# 10_Misc.net
KiCad netlist of a schematic drawn in Altium Designer
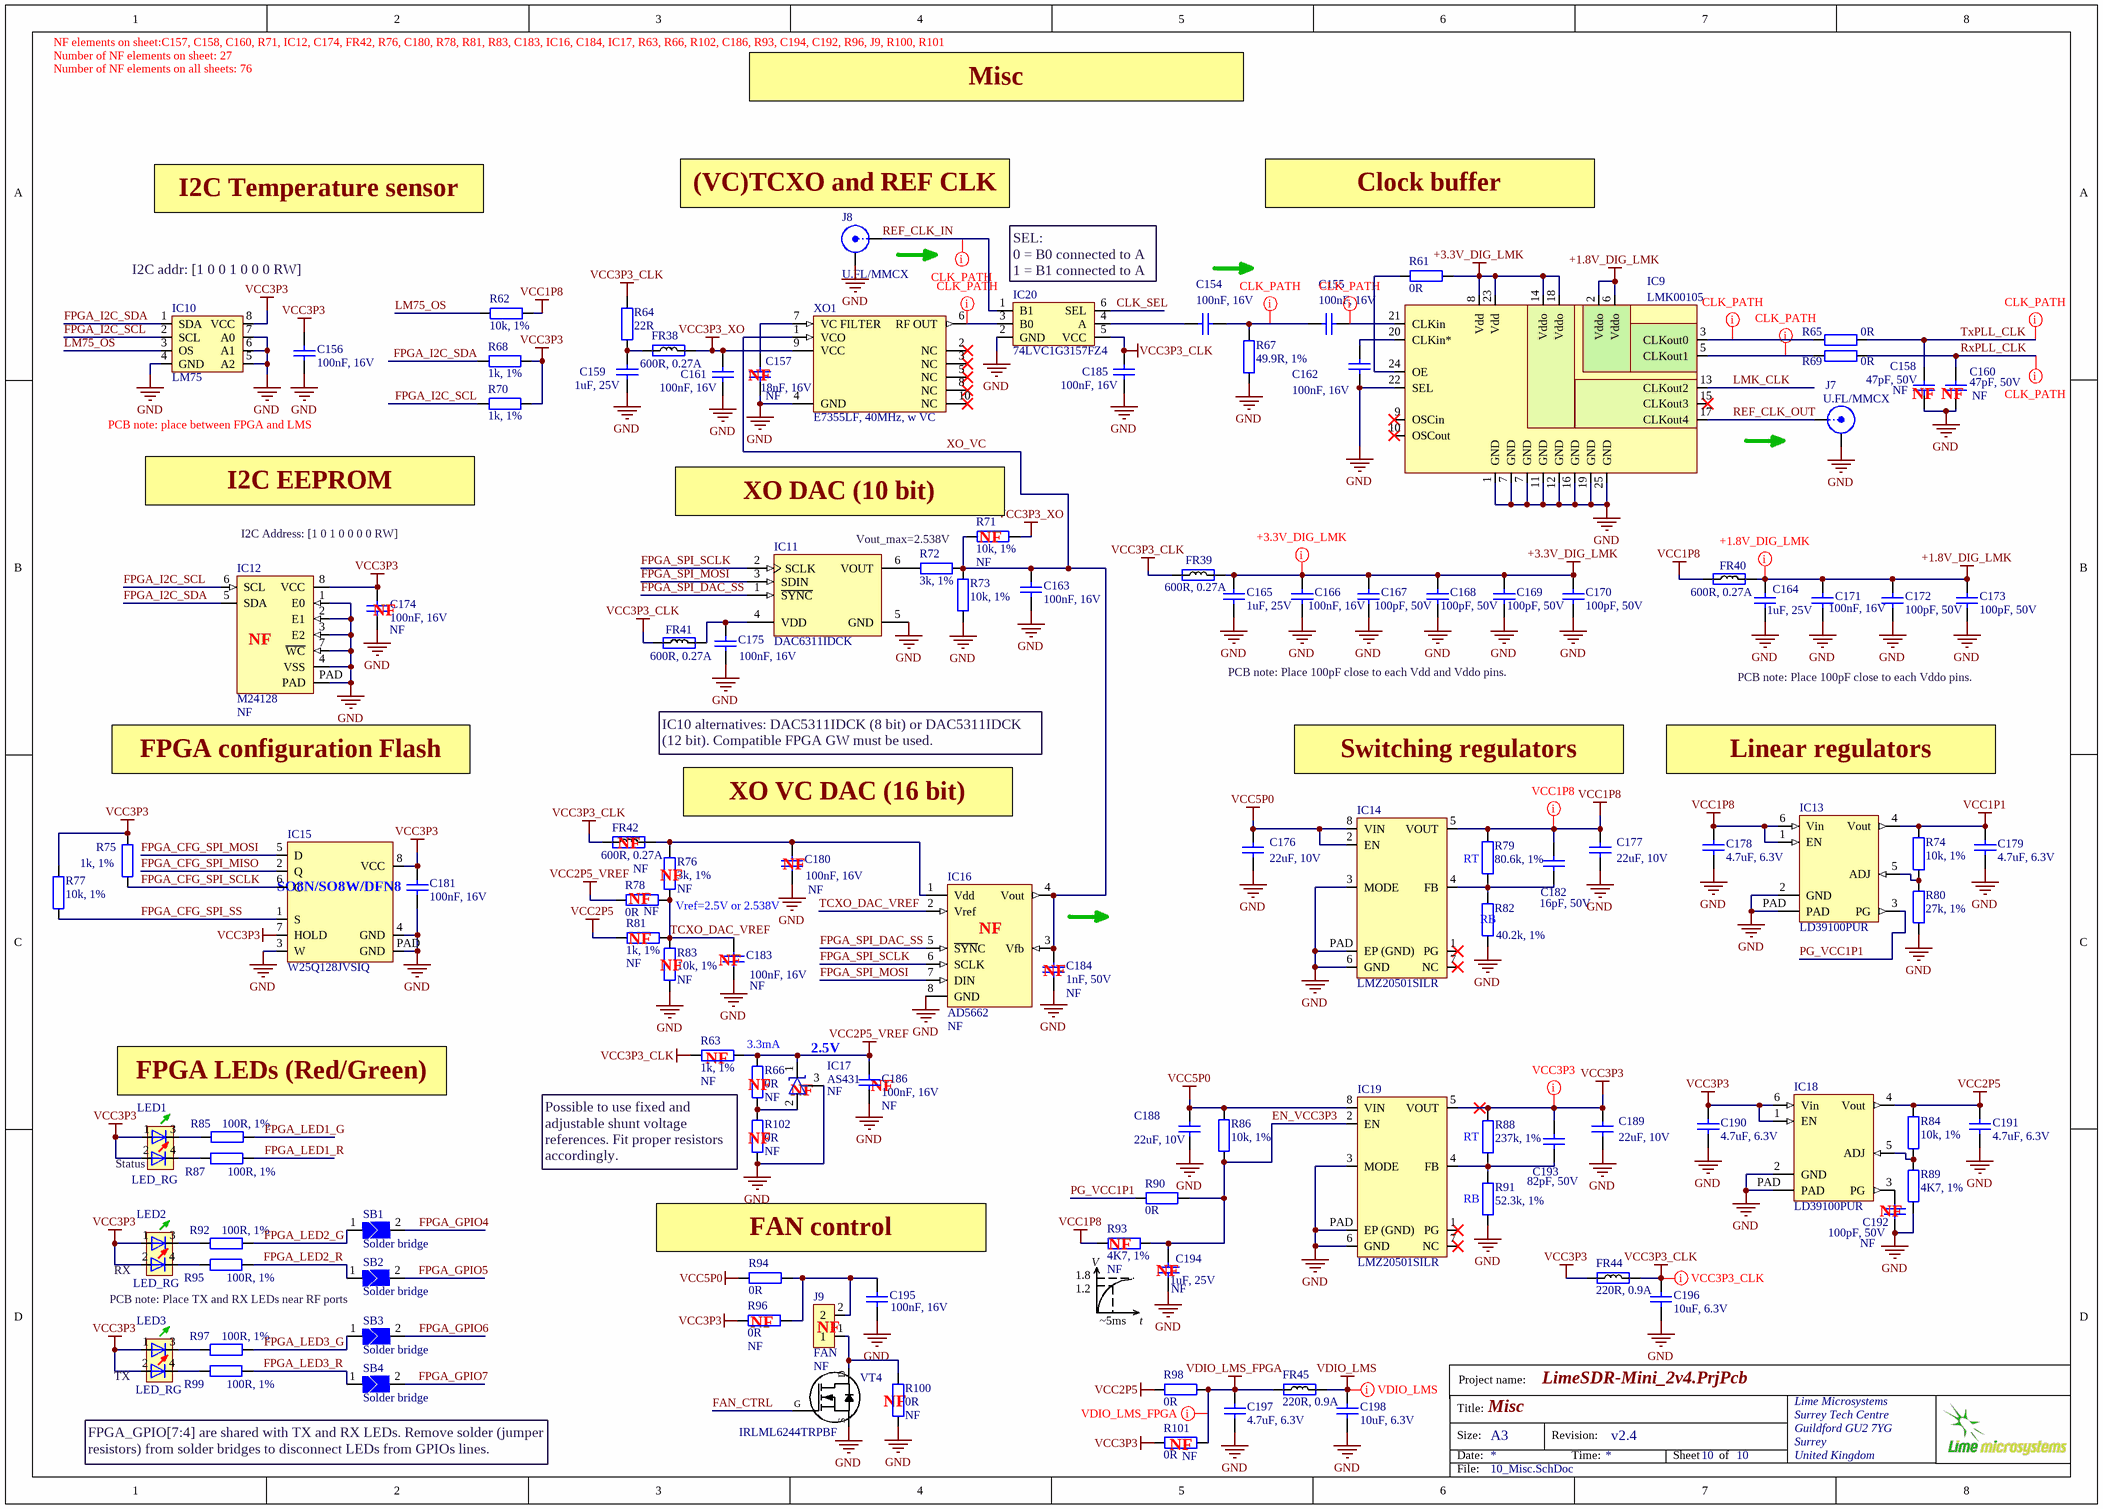
[diagram p0: 10_Misc.SchDoc]

(export (version "E")
  (design (tool "Eeschema 10.0.6"))
  (components
    (comp (ref "C154")
      (value "100nF, 16V")
      (footprint "CAP0402")
      (fields
        (field (name "MANUFACTURER") "Murata Electronics")
        (field (name "TOLERANCE") "10 %")
        (field (name "MANUFACTURER PART NUMBER") "GRM155R71C104KA88D")
      )
      (libsource (lib "LimeMicroAltiumLib_schLib") (part "Cap_0402"))
    )
    (comp (ref "C155")
      (value "100nF, 16V")
      (footprint "CAP0402")
      (fields
        (field (name "MANUFACTURER") "Murata Electronics")
        (field (name "TOLERANCE") "10 %")
        (field (name "MANUFACTURER PART NUMBER") "GRM155R71C104KA88D")
      )
      (libsource (lib "LimeMicroAltiumLib_schLib") (part "Cap_0402"))
    )
    (comp (ref "C156")
      (value "100nF, 16V")
      (footprint "CAP0402")
      (fields
        (field (name "TOLERANCE") "10 %")
        (field (name "MANUFACTURER") "Murata Electronics")
        (field (name "MANUFACTURER PART NUMBER") "GRM155R71C104KA88D")
      )
      (libsource (lib "LimeFPGAboard_schLib") (part "Cap_0603"))
    )
    (comp (ref "C157")
      (value "18nF, 16V")
      (footprint "CAP0402")
      (fields
        (field (name "ASSEMBLY INFO") "NF")
        (field (name "MANUFACTURER") "Yageo")
        (field (name "TOLERANCE") "±10%")
      )
      (libsource (lib "LimeMicroAltiumLib_schLib") (part "Cap_0402"))
    )
    (comp (ref "C158")
      (value "47pF, 50V")
      (footprint "CAP0402")
      (fields
        (field (name "TOLERANCE") "±1%")
        (field (name "MANUFACTURER") "TDK Corporation")
        (field (name "ASSEMBLY INFO") "NF")
      )
      (libsource (lib "LimeMicroAltiumLib_schLib") (part "Cap_0402"))
    )
    (comp (ref "C159")
      (value "1uF, 25V")
      (footprint "CAP0402")
      (fields (field (name "MANUFACTURER") "TDK"))
      (libsource (lib "LimeMicroAltiumLib_schLib") (part "Cap_0402"))
    )
    (comp (ref "C160")
      (value "47pF, 50V")
      (footprint "CAP0402")
      (fields
        (field (name "TOLERANCE") "±1%")
        (field (name "MANUFACTURER") "TDK Corporation")
        (field (name "ASSEMBLY INFO") "NF")
      )
      (libsource (lib "LimeMicroAltiumLib_schLib") (part "Cap_0402"))
    )
    (comp (ref "C161")
      (value "100nF, 16V")
      (footprint "CAP0402")
      (fields
        (field (name "MANUFACTURER") "Murata Electronics")
        (field (name "TOLERANCE") "10 %")
        (field (name "MANUFACTURER PART NUMBER") "GRM155R71C104KA88D")
      )
      (libsource (lib "LimeMicroAltiumLib_schLib") (part "Cap_0402"))
    )
    (comp (ref "C162")
      (value "100nF, 16V")
      (footprint "CAP0402")
      (fields
        (field (name "MANUFACTURER") "Murata Electronics")
        (field (name "TOLERANCE") "10 %")
        (field (name "MANUFACTURER PART NUMBER") "GRM155R71C104KA88D")
      )
      (libsource (lib "LimeMicroAltiumLib_schLib") (part "Cap_0402"))
    )
    (comp (ref "C163")
      (value "100nF, 16V")
      (footprint "CAP0402")
      (fields
        (field (name "MANUFACTURER") "Murata Electronics")
        (field (name "TOLERANCE") "10 %")
        (field (name "MANUFACTURER PART NUMBER") "GRM155R71C104KA88D")
      )
      (libsource (lib "LimeMicroAltiumLib_schLib") (part "Cap_0402"))
    )
    (comp (ref "C164")
      (value "1uF, 25V")
      (footprint "CAP0402")
      (fields (field (name "MANUFACTURER") "TDK"))
      (libsource (lib "LimeMicroAltiumLib_schLib") (part "Cap_0402"))
    )
    (comp (ref "C165")
      (value "1uF, 25V")
      (footprint "CAP0402")
      (fields (field (name "MANUFACTURER") "TDK"))
      (libsource (lib "LimeMicroAltiumLib_schLib") (part "Cap_0402"))
    )
    (comp (ref "C166")
      (value "100nF, 16V")
      (footprint "CAP0402")
      (fields
        (field (name "MANUFACTURER") "Murata Electronics")
        (field (name "TOLERANCE") "10 %")
        (field (name "MANUFACTURER PART NUMBER") "GRM155R71C104KA88D")
      )
      (libsource (lib "LimeMicroAltiumLib_schLib") (part "Cap_0402"))
    )
    (comp (ref "C167")
      (value "100pF, 50V")
      (footprint "CAP0402")
      (fields (field (name "MANUFACTURER") "Yageo") (field (name "TOLERANCE") "±5%"))
      (libsource (lib "LimeMicroAltiumLib_schLib") (part "Cap_0402"))
    )
    (comp (ref "C168")
      (value "100pF, 50V")
      (footprint "CAP0402")
      (fields (field (name "MANUFACTURER") "Yageo") (field (name "TOLERANCE") "±5%"))
      (libsource (lib "LimeMicroAltiumLib_schLib") (part "Cap_0402"))
    )
    (comp (ref "C169")
      (value "100pF, 50V")
      (footprint "CAP0402")
      (fields (field (name "MANUFACTURER") "Yageo") (field (name "TOLERANCE") "±5%"))
      (libsource (lib "LimeMicroAltiumLib_schLib") (part "Cap_0402"))
    )
    (comp (ref "C170")
      (value "100pF, 50V")
      (footprint "CAP0402")
      (fields (field (name "MANUFACTURER") "Yageo") (field (name "TOLERANCE") "±5%"))
      (libsource (lib "LimeMicroAltiumLib_schLib") (part "Cap_0402"))
    )
    (comp (ref "C171")
      (value "100nF, 16V")
      (footprint "CAP0402")
      (fields
        (field (name "MANUFACTURER") "Murata Electronics")
        (field (name "TOLERANCE") "10 %")
        (field (name "MANUFACTURER PART NUMBER") "GRM155R71C104KA88D")
      )
      (libsource (lib "LimeMicroAltiumLib_schLib") (part "Cap_0402"))
    )
    (comp (ref "C172")
      (value "100pF, 50V")
      (footprint "CAP0402")
      (fields (field (name "MANUFACTURER") "Yageo") (field (name "TOLERANCE") "±5%"))
      (libsource (lib "LimeMicroAltiumLib_schLib") (part "Cap_0402"))
    )
    (comp (ref "C173")
      (value "100pF, 50V")
      (footprint "CAP0402")
      (fields (field (name "MANUFACTURER") "Yageo") (field (name "TOLERANCE") "±5%"))
      (libsource (lib "LimeMicroAltiumLib_schLib") (part "Cap_0402"))
    )
    (comp (ref "C174")
      (value "100nF, 16V")
      (footprint "CAP0402")
      (fields
        (field (name "TOLERANCE") "10 %")
        (field (name "MANUFACTURER") "Murata Electronics")
        (field (name "MANUFACTURER PART NUMBER") "GRM155R71C104KA88D")
        (field (name "ASSEMBLY INFO") "NF")
      )
      (libsource (lib "LimeFPGAboard_schLib") (part "Cap_0603"))
    )
    (comp (ref "C175")
      (value "100nF, 16V")
      (footprint "CAP0402")
      (fields
        (field (name "TOLERANCE") "10 %")
        (field (name "MANUFACTURER") "Murata Electronics")
        (field (name "MANUFACTURER PART NUMBER") "GRM155R71C104KA88D")
      )
      (libsource (lib "LimeFPGAboard_schLib") (part "Cap_0603"))
    )
    (comp (ref "C176")
      (value "22uF, 10V")
      (footprint "CAP0603")
      (fields (field (name "TOLERANCE") "20 %") (field (name "MANUFACTURER") "TDK Corporation"))
      (libsource (lib "LimeFPGAboard_schLib") (part "Cap_0603"))
    )
    (comp (ref "C177")
      (value "22uF, 10V")
      (footprint "CAP0603")
      (fields (field (name "TOLERANCE") "20 %") (field (name "MANUFACTURER") "TDK Corporation"))
      (libsource (lib "LimeFPGAboard_schLib") (part "Cap_0603"))
    )
    (comp (ref "C178")
      (value "4.7uF, 6.3V")
      (footprint "CAP0402")
      (fields
        (field (name "MANUFACTURER") "Murata Electronics North America")
        (field (name "TOLERANCE") "±20%")
      )
      (libsource (lib "LimeMicroAltiumLib_schLib") (part "Cap_0402"))
    )
    (comp (ref "C179")
      (value "4.7uF, 6.3V")
      (footprint "CAP0402")
      (fields
        (field (name "MANUFACTURER") "Murata Electronics North America")
        (field (name "TOLERANCE") "±20%")
      )
      (libsource (lib "LimeMicroAltiumLib_schLib") (part "Cap_0402"))
    )
    (comp (ref "C180")
      (value "100nF, 16V")
      (footprint "CAP0402")
      (fields
        (field (name "TOLERANCE") "10 %")
        (field (name "MANUFACTURER") "Murata Electronics")
        (field (name "MANUFACTURER PART NUMBER") "GRM155R71C104KA88D")
        (field (name "ASSEMBLY INFO") "NF")
      )
      (libsource (lib "LimeFPGAboard_schLib") (part "Cap_0603"))
    )
    (comp (ref "C181")
      (value "100nF, 16V")
      (footprint "CAP0402")
      (fields
        (field (name "TOLERANCE") "10 %")
        (field (name "MANUFACTURER") "Murata Electronics")
        (field (name "MANUFACTURER PART NUMBER") "GRM155R71C104KA88D")
      )
      (libsource (lib "LimeFPGAboard_schLib") (part "Cap_0603"))
    )
    (comp (ref "C182")
      (value "16pF, 50V")
      (footprint "CAP0402")
      (fields (field (name "MANUFACTURER") "Yageo") (field (name "TOLERANCE") "5%"))
      (libsource (lib "LimeMicroAltiumLib_schLib") (part "Cap_0402"))
    )
    (comp (ref "C183")
      (value "100nF, 16V")
      (footprint "CAP0402")
      (fields
        (field (name "TOLERANCE") "10 %")
        (field (name "MANUFACTURER") "Murata Electronics")
        (field (name "ASSEMBLY INFO") "NF")
      )
      (libsource (lib "") (part "Cap_0603_1"))
    )
    (comp (ref "C184")
      (value "1nF, 50V")
      (footprint "CAP0402")
      (fields
        (field (name "ASSEMBLY INFO") "NF")
        (field (name "TOLERANCE") "10 %")
        (field (name "MANUFACTURER") "Murata Electronics")
      )
      (libsource (lib "") (part "Cap_0402_1"))
    )
    (comp (ref "C185")
      (value "100nF, 16V")
      (footprint "CAP0402")
      (fields
        (field (name "MANUFACTURER") "Murata Electronics")
        (field (name "TOLERANCE") "10 %")
        (field (name "MANUFACTURER PART NUMBER") "GRM155R71C104KA88D")
      )
      (libsource (lib "LimeMicroAltiumLib_schLib") (part "Cap_0402"))
    )
    (comp (ref "C186")
      (value "100nF, 16V")
      (footprint "CAP0402")
      (fields
        (field (name "TOLERANCE") "10 %")
        (field (name "MANUFACTURER") "Murata Electronics")
        (field (name "ASSEMBLY INFO") "NF")
      )
      (libsource (lib "") (part "Cap_0603_1"))
    )
    (comp (ref "C188")
      (value "22uF, 10V")
      (footprint "CAP0603")
      (fields (field (name "TOLERANCE") "20 %") (field (name "MANUFACTURER") "TDK Corporation"))
      (libsource (lib "LimeFPGAboard_schLib") (part "Cap_0603"))
    )
    (comp (ref "C189")
      (value "22uF, 10V")
      (footprint "CAP0603")
      (fields (field (name "TOLERANCE") "20 %") (field (name "MANUFACTURER") "TDK Corporation"))
      (libsource (lib "LimeFPGAboard_schLib") (part "Cap_0603"))
    )
    (comp (ref "C190")
      (value "4.7uF, 6.3V")
      (footprint "CAP0402")
      (fields
        (field (name "MANUFACTURER") "Murata Electronics North America")
        (field (name "TOLERANCE") "±20%")
      )
      (libsource (lib "LimeMicroAltiumLib_schLib") (part "Cap_0402"))
    )
    (comp (ref "C191")
      (value "4.7uF, 6.3V")
      (footprint "CAP0402")
      (fields
        (field (name "MANUFACTURER") "Murata Electronics North America")
        (field (name "TOLERANCE") "±20%")
      )
      (libsource (lib "LimeMicroAltiumLib_schLib") (part "Cap_0402"))
    )
    (comp (ref "C192")
      (value "100pF, 50V")
      (footprint "CAP0402")
      (fields
        (field (name "ASSEMBLY INFO") "NF")
        (field (name "MANUFACTURER") "Yageo")
        (field (name "TOLERANCE") "±5%")
      )
      (libsource (lib "LimeMicroAltiumLib_schLib") (part "Cap_0402"))
    )
    (comp (ref "C193")
      (value "82pF, 50V")
      (footprint "CAP0402")
      (fields (field (name "MANUFACTURER") "Taiyo Yuden"))
      (libsource (lib "LimeMicroAltiumLib_schLib") (part "Cap_0402"))
    )
    (comp (ref "C194")
      (value "1uF, 25V")
      (footprint "CAP0402")
      (fields (field (name "ASSEMBLY INFO") "NF") (field (name "MANUFACTURER") "TDK"))
      (libsource (lib "LimeMicroAltiumLib_schLib") (part "Cap_0402"))
    )
    (comp (ref "C195")
      (value "100nF, 16V")
      (footprint "CAP0402")
      (fields
        (field (name "TOLERANCE") "10 %")
        (field (name "MANUFACTURER") "Murata Electronics")
        (field (name "MANUFACTURER PART NUMBER") "GRM155R71C104KA88D")
      )
      (libsource (lib "LimeFPGAboard_schLib") (part "Cap_0603"))
    )
    (comp (ref "C196")
      (value "10uF, 6.3V")
      (footprint "CAP0603")
      (fields (field (name "TOLERANCE") "±20%") (field (name "MANUFACTURER") "Yageo"))
      (libsource (lib "LimeFPGAboard_schLib") (part "Cap_0603"))
    )
    (comp (ref "C197")
      (value "4.7uF, 6.3V")
      (footprint "CAP0402")
      (fields
        (field (name "MANUFACTURER") "Murata Electronics North America")
        (field (name "TOLERANCE") "±20%")
      )
      (libsource (lib "LimeMicroAltiumLib_schLib") (part "Cap_0402"))
    )
    (comp (ref "C198")
      (value "10uF, 6.3V")
      (footprint "CAP0603")
      (fields (field (name "TOLERANCE") "±20%") (field (name "MANUFACTURER") "Yageo"))
      (libsource (lib "LimeFPGAboard_schLib") (part "Cap_0603"))
    )
    (comp (ref "FR38")
      (value "600R, 0.27A")
      (footprint "RES0201")
      (fields (field (name "MANUFACTURER") "Taiyo Yuden"))
      (libsource (lib "LimeMicroAltiumLib_schLib") (part "Ferrite"))
    )
    (comp (ref "FR39")
      (value "600R, 0.27A")
      (footprint "RES0201")
      (fields (field (name "MANUFACTURER") "Taiyo Yuden"))
      (libsource (lib "LimeMicroAltiumLib_schLib") (part "Ferrite"))
    )
    (comp (ref "FR40")
      (value "600R, 0.27A")
      (footprint "RES0201")
      (fields (field (name "MANUFACTURER") "Taiyo Yuden"))
      (libsource (lib "LimeMicroAltiumLib_schLib") (part "Ferrite"))
    )
    (comp (ref "FR41")
      (value "600R, 0.27A")
      (footprint "RES0201")
      (fields (field (name "MANUFACTURER") "Taiyo Yuden"))
      (libsource (lib "LimeMicroAltiumLib_schLib") (part "Ferrite"))
    )
    (comp (ref "FR42")
      (value "600R, 0.27A")
      (footprint "RES0201")
      (fields (field (name "MANUFACTURER") "Taiyo Yuden") (field (name "ASSEMBLY INFO") "NF"))
      (libsource (lib "LimeMicroAltiumLib_schLib") (part "Ferrite"))
    )
    (comp (ref "FR44")
      (value "220R, 0.9A")
      (footprint "RES0402")
      (fields (field (name "MANUFACTURER") "TDK Corporation"))
      (libsource (lib "LimeFPGAboard_schLib") (part "Ferrite"))
    )
    (comp (ref "FR45")
      (value "220R, 0.9A")
      (footprint "RES0402")
      (fields (field (name "MANUFACTURER") "TDK Corporation"))
      (libsource (lib "LimeFPGAboard_schLib") (part "Ferrite"))
    )
    (comp (ref "IC9")
      (value "LMK00105")
      (footprint "LMK00105SQ")
      (fields (field (name "MANUFACTURER") "Texas Instruments"))
      (libsource (lib "LimeMicroAltiumLib_schLib") (part "LMK00105"))
    )
    (comp (ref "IC10")
      (value "LM75")
      (footprint "HWSON8_LM75")
      (fields (field (name "MANUFACTURER") "NXP Semiconductors"))
      (libsource (lib "LimeMicroAltiumLib_schLib") (part "LM75"))
    )
    (comp (ref "IC11")
      (value "DAC6311IDCK")
      (footprint "AD5601_SOT23-6")
      (fields (field (name "MANUFACTURER") "Texas Instruments"))
      (libsource (lib "LimeMicroAltiumLib_schLib") (part "AD5601BKSZ-REEL7"))
    )
    (comp (ref "IC12")
      (value "M24128")
      (footprint "M24128-DFMC6TG")
      (fields (field (name "MANUFACTURER") "STMicroelectronics") (field (name "ASSEMBLY INFO") "NF"))
      (libsource (lib "LimeMicroAltiumLib_schLib") (part "M24128-DFMC6TG"))
    )
    (comp (ref "IC13")
      (value "LD39100PUR")
      (footprint "LD39100PUR")
      (fields (field (name "MANUFACTURER") "STMicroelectronics"))
      (libsource (lib "LimeMicroAltiumLib_schLib") (part "LD39100PUR"))
    )
    (comp (ref "IC14")
      (value "LMZ20501SILR")
      (footprint "LMZ20501SILR_DC-DC_8-SMD")
      (fields (field (name "MANUFACTURER") "Texas Instruments"))
      (libsource (lib "LimeMicroAltiumLib_schLib_r04") (part "LMZ20501SILR_DC-DC"))
    )
    (comp (ref "IC15")
      (value "W25Q128JVSIQ")
      (footprint "S25FL164K_WSON8_DFN6")
      (fields (field (name "MANUFACTURER") "Winbond"))
      (libsource (lib "LimeMicroAltiumLib_schLib_r03") (part "M25P40_with_pad"))
    )
    (comp (ref "IC16")
      (value "AD5662")
      (footprint "AD5662_SOT23-8")
      (fields (field (name "MANUFACTURER") "Analog Devices Inc.") (field (name "ASSEMBLY INFO") "NF"))
      (libsource (lib "LimeMicroAltiumLib_schLib") (part "AD5662"))
    )
    (comp (ref "IC17")
      (value "AS431")
      (footprint "SOT23-3_V3")
      (fields
        (field (name "ASSEMBLY INFO") "NF")
        (field (name "MANUFACTURER") "Diodes")
        (field (name "TOLERANCE") "0.5%")
      )
      (libsource (lib "LimeMicroAltiumLib_schLib_r05") (part "VOLTAGE_REFERENCE_UNIVERSAL"))
    )
    (comp (ref "IC18")
      (value "LD39100PUR")
      (footprint "LD39100PUR")
      (fields (field (name "MANUFACTURER") "STMicroelectronics"))
      (libsource (lib "LimeMicroAltiumLib_schLib") (part "LD39100PUR"))
    )
    (comp (ref "IC19")
      (value "LMZ20501SILR")
      (footprint "LMZ20501SILR_DC-DC_8-SMD")
      (fields (field (name "MANUFACTURER") "Texas Instruments"))
      (libsource (lib "LimeMicroAltiumLib_schLib_r04") (part "LMZ20501SILR_DC-DC"))
    )
    (comp (ref "IC20")
      (value "74LVC1G3157FZ4")
      (footprint "74LVC1G3157FZ4_SPDT_SW_DFN1410-6")
      (fields (field (name "MANUFACTURER") "Diodes"))
      (libsource (lib "LimeMicroAltiumLib_schLib_r04") (part "74LVC1G3157FZ4_SPDT_SW"))
    )
    (comp (ref "J7")
      (value "U.FL/MMCX")
      (footprint "MMCX_UFL_conn_u")
      (description "CONN UMC RCPT STR 50 OHM SMD")
      (fields (field (name "MANUFACTURER") "Molex, LLC"))
      (libsource (lib "LimeMicroAltiumLib_schLib") (part "RF_IF_connector"))
    )
    (comp (ref "J8")
      (value "U.FL/MMCX")
      (footprint "MMCX_UFL_conn_u")
      (description "CONN UMC RCPT STR 50 OHM SMD")
      (fields (field (name "MANUFACTURER") "Molex, LLC"))
      (libsource (lib "LimeMicroAltiumLib_schLib") (part "RF_IF_connector"))
    )
    (comp (ref "J9")
      (value "FAN")
      (footprint "Header2x1_TH_v2")
      (fields (field (name "ASSEMBLY INFO") "NF") (field (name "MANUFACTURER") "3M"))
      (libsource (lib "LimeFPGAboard_schLib") (part "Jumper"))
    )
    (comp (ref "LED1")
      (value "LED_RG")
      (footprint "LED-2x0603")
      (fields (field (name "MANUFACTURER") "Avago Technologies US Inc."))
      (libsource (lib "LimeMicroAltiumLib_schLib") (part "LED_green_red_SMD"))
    )
    (comp (ref "LED2")
      (value "LED_RG")
      (footprint "LED-2x0603")
      (fields (field (name "MANUFACTURER") "Avago Technologies US Inc."))
      (libsource (lib "LimeMicroAltiumLib_schLib") (part "LED_green_red_SMD"))
    )
    (comp (ref "LED3")
      (value "LED_RG")
      (footprint "LED-2x0603")
      (fields (field (name "MANUFACTURER") "Avago Technologies US Inc."))
      (libsource (lib "LimeMicroAltiumLib_schLib") (part "LED_green_red_SMD"))
    )
    (comp (ref "R61")
      (value "0R")
      (footprint "RES0402")
      (fields (field (name "MANUFACTURER") "Yageo") (field (name "TOLERANCE") "Jumper"))
      (libsource (lib "") (part "Res_0402_1"))
    )
    (comp (ref "R62")
      (value "10k, 1%")
      (footprint "RES0402")
      (fields (field (name "MANUFACTURER") "Yageo") (field (name "TOLERANCE") "±1%"))
      (libsource (lib "") (part "Res_0402_1"))
    )
    (comp (ref "R63")
      (value "1k, 1%")
      (footprint "RES0402")
      (fields
        (field (name "ASSEMBLY INFO") "NF")
        (field (name "MANUFACTURER") "Stackpole Electronics Inc")
        (field (name "TOLERANCE") "±1%")
      )
      (libsource (lib "") (part "Res_0402_1"))
    )
    (comp (ref "R64")
      (value "22R")
      (footprint "RES0402")
      (fields (field (name "TOLERANCE") "±1%") (field (name "MANUFACTURER") "Yageo"))
      (libsource (lib "LimeFPGAboard_schLib") (part "Res_0402"))
    )
    (comp (ref "R65")
      (value "0R")
      (footprint "RES0402")
      (fields (field (name "MANUFACTURER") "Yageo") (field (name "TOLERANCE") "Jumper"))
      (libsource (lib "LimeFPGAboard_schLib") (part "Res_0402"))
    )
    (comp (ref "R66")
      (value "0R")
      (footprint "RES0402")
      (fields
        (field (name "ASSEMBLY INFO") "NF")
        (field (name "MANUFACTURER") "Yageo")
        (field (name "TOLERANCE") "Jumper")
      )
      (libsource (lib "") (part "Res_0402_1"))
    )
    (comp (ref "R67")
      (value "49.9R, 1%")
      (footprint "RES0402")
      (fields
        (field (name "TOLERANCE") "±1%")
        (field (name "MANUFACTURER") "Samsung Electro-Mechanics America, Inc.")
      )
      (libsource (lib "") (part "Res_0402_1"))
    )
    (comp (ref "R68")
      (value "1k, 1%")
      (footprint "RES0402")
      (fields (field (name "MANUFACTURER") "Stackpole Electronics Inc") (field (name "TOLERANCE") "±1%"))
      (libsource (lib "") (part "Res_0402_1"))
    )
    (comp (ref "R69")
      (value "0R")
      (footprint "RES0402")
      (fields (field (name "MANUFACTURER") "Yageo") (field (name "TOLERANCE") "Jumper"))
      (libsource (lib "LimeFPGAboard_schLib") (part "Res_0402"))
    )
    (comp (ref "R70")
      (value "1k, 1%")
      (footprint "RES0402")
      (fields (field (name "MANUFACTURER") "Stackpole Electronics Inc") (field (name "TOLERANCE") "±1%"))
      (libsource (lib "") (part "Res_0402_1"))
    )
    (comp (ref "R71")
      (value "10k, 1%")
      (footprint "RES0402")
      (fields
        (field (name "ASSEMBLY INFO") "NF")
        (field (name "MANUFACTURER") "Yageo")
        (field (name "TOLERANCE") "±1%")
      )
      (libsource (lib "") (part "Res_0402_1"))
    )
    (comp (ref "R72")
      (value "3k, 1%")
      (footprint "RES0402")
      (fields (field (name "TOLERANCE") "±1%") (field (name "MANUFACTURER") "Vishay Dale"))
      (libsource (lib "") (part "Res_0402_1"))
    )
    (comp (ref "R73")
      (value "10k, 1%")
      (footprint "RES0402")
      (fields (field (name "MANUFACTURER") "Yageo") (field (name "TOLERANCE") "±1%"))
      (libsource (lib "") (part "Res_0402_1"))
    )
    (comp (ref "R74")
      (value "10k, 1%")
      (footprint "RES0402")
      (fields (field (name "MANUFACTURER") "Yageo") (field (name "TOLERANCE") "±1%"))
      (libsource (lib "") (part "Res_0402_1"))
    )
    (comp (ref "R75")
      (value "1k, 1%")
      (footprint "RES0402")
      (fields (field (name "MANUFACTURER") "Stackpole Electronics Inc") (field (name "TOLERANCE") "±1%"))
      (libsource (lib "") (part "Res_0402_1"))
    )
    (comp (ref "R76")
      (value "3k, 1%")
      (footprint "RES0402")
      (fields
        (field (name "ASSEMBLY INFO") "NF")
        (field (name "TOLERANCE") "±1%")
        (field (name "MANUFACTURER") "Vishay Dale")
      )
      (libsource (lib "LimeMicroAltiumLib_schLib") (part "Res_0402"))
    )
    (comp (ref "R77")
      (value "10k, 1%")
      (footprint "RES0402")
      (fields (field (name "MANUFACTURER") "Yageo") (field (name "TOLERANCE") "±1%"))
      (libsource (lib "") (part "Res_0402_1"))
    )
    (comp (ref "R78")
      (value "0R")
      (footprint "RES0402")
      (fields
        (field (name "ASSEMBLY INFO") "NF")
        (field (name "MANUFACTURER") "Yageo")
        (field (name "TOLERANCE") "Jumper")
      )
      (libsource (lib "") (part "Res_0402_1"))
    )
    (comp (ref "R79")
      (value "80.6k, 1%")
      (footprint "RES0402")
      (fields (field (name "MANUFACTURER") "Stackpole Electronics") (field (name "TOLERANCE") "1%"))
      (libsource (lib "") (part "Res_0402_1"))
    )
    (comp (ref "R80")
      (value "27k, 1%")
      (footprint "RES0402")
      (fields (field (name "MANUFACTURER") "Yageo") (field (name "TOLERANCE") "1%"))
      (libsource (lib "LimeFPGAboard_schLib") (part "Res_0402"))
    )
    (comp (ref "R81")
      (value "1k, 1%")
      (footprint "RES0402")
      (fields
        (field (name "ASSEMBLY INFO") "NF")
        (field (name "MANUFACTURER") "Stackpole Electronics Inc")
        (field (name "TOLERANCE") "±1%")
      )
      (libsource (lib "LimeMicroAltiumLib_schLib") (part "Res_0402"))
    )
    (comp (ref "R82")
      (value "40.2k, 1%")
      (footprint "RES0402")
      (fields (field (name "MANUFACTURER") "Yageo") (field (name "TOLERANCE") "1%"))
      (libsource (lib "") (part "Res_0402_1"))
    )
    (comp (ref "R83")
      (value "10k, 1%")
      (footprint "RES0402")
      (fields
        (field (name "ASSEMBLY INFO") "NF")
        (field (name "MANUFACTURER") "Yageo")
        (field (name "TOLERANCE") "±1%")
      )
      (libsource (lib "LimeMicroAltiumLib_schLib") (part "Res_0402"))
    )
    (comp (ref "R84")
      (value "10k, 1%")
      (footprint "RES0402")
      (fields (field (name "MANUFACTURER") "Yageo") (field (name "TOLERANCE") "±1%"))
      (libsource (lib "") (part "Res_0402_1"))
    )
    (comp (ref "R85")
      (value "100R, 1%")
      (footprint "RES0402")
      (fields (field (name "TOLERANCE") "±1%") (field (name "MANUFACTURER") "Stackpole Electronics Inc."))
      (libsource (lib "") (part "Res_0402_1"))
    )
    (comp (ref "R86")
      (value "10k, 1%")
      (footprint "RES0402")
      (fields (field (name "MANUFACTURER") "Yageo") (field (name "TOLERANCE") "±1%"))
      (libsource (lib "") (part "Res_0402_1"))
    )
    (comp (ref "R87")
      (value "100R, 1%")
      (footprint "RES0402")
      (fields (field (name "TOLERANCE") "±1%") (field (name "MANUFACTURER") "Stackpole Electronics Inc."))
      (libsource (lib "") (part "Res_0402_1"))
    )
    (comp (ref "R88")
      (value "237k, 1%")
      (footprint "RES0402")
      (fields (field (name "MANUFACTURER") "Yageo") (field (name "TOLERANCE") "1%"))
      (libsource (lib "") (part "Res_0402_1"))
    )
    (comp (ref "R89")
      (value "4K7, 1%")
      (footprint "RES0402")
      (fields (field (name "MANUFACTURER") "Yageo") (field (name "TOLERANCE") "±1%"))
      (libsource (lib "LimeFPGAboard_schLib") (part "Res_0402"))
    )
    (comp (ref "R90")
      (value "0R")
      (footprint "RES0402")
      (fields (field (name "MANUFACTURER") "Yageo") (field (name "TOLERANCE") "Jumper"))
      (libsource (lib "") (part "Res_0402_1"))
    )
    (comp (ref "R91")
      (value "52.3k, 1%")
      (footprint "RES0402")
      (fields (field (name "MANUFACTURER") "Panasonic") (field (name "TOLERANCE") "1%"))
      (libsource (lib "") (part "Res_0402_1"))
    )
    (comp (ref "R92")
      (value "100R, 1%")
      (footprint "RES0402")
      (fields (field (name "TOLERANCE") "±1%") (field (name "MANUFACTURER") "Stackpole Electronics Inc."))
      (libsource (lib "") (part "Res_0402_1"))
    )
    (comp (ref "R93")
      (value "4K7, 1%")
      (footprint "RES0402")
      (fields
        (field (name "MANUFACTURER") "Yageo")
        (field (name "TOLERANCE") "±1%")
        (field (name "ASSEMBLY INFO") "NF")
      )
      (libsource (lib "LimeFPGAboard_schLib") (part "Res_0402"))
    )
    (comp (ref "R94")
      (value "0R")
      (footprint "RES0402")
      (fields (field (name "MANUFACTURER") "Yageo") (field (name "TOLERANCE") "Jumper"))
      (libsource (lib "") (part "Res_0402_1"))
    )
    (comp (ref "R95")
      (value "100R, 1%")
      (footprint "RES0402")
      (fields (field (name "TOLERANCE") "±1%") (field (name "MANUFACTURER") "Stackpole Electronics Inc."))
      (libsource (lib "") (part "Res_0402_1"))
    )
    (comp (ref "R96")
      (value "0R")
      (footprint "RES0402")
      (fields
        (field (name "ASSEMBLY INFO") "NF")
        (field (name "MANUFACTURER") "Yageo")
        (field (name "TOLERANCE") "Jumper")
      )
      (libsource (lib "") (part "Res_0402_1"))
    )
    (comp (ref "R97")
      (value "100R, 1%")
      (footprint "RES0402")
      (fields (field (name "TOLERANCE") "±1%") (field (name "MANUFACTURER") "Stackpole Electronics Inc."))
      (libsource (lib "") (part "Res_0402_1"))
    )
    (comp (ref "R98")
      (value "0R")
      (footprint "RES0402")
      (fields (field (name "MANUFACTURER") "Yageo") (field (name "TOLERANCE") "Jumper"))
      (libsource (lib "LimeFPGAboard_schLib") (part "Res_0402"))
    )
    (comp (ref "R99")
      (value "100R, 1%")
      (footprint "RES0402")
      (fields (field (name "TOLERANCE") "±1%") (field (name "MANUFACTURER") "Stackpole Electronics Inc."))
      (libsource (lib "") (part "Res_0402_1"))
    )
    (comp (ref "R100")
      (value "0R")
      (footprint "RES0402")
      (fields
        (field (name "ASSEMBLY INFO") "NF")
        (field (name "MANUFACTURER") "Yageo")
        (field (name "TOLERANCE") "Jumper")
      )
      (libsource (lib "") (part "Res_0402_1"))
    )
    (comp (ref "R101")
      (value "0R")
      (footprint "RES0402")
      (fields
        (field (name "MANUFACTURER") "Yageo")
        (field (name "ASSEMBLY INFO") "NF")
        (field (name "TOLERANCE") "Jumper")
      )
      (libsource (lib "LimeFPGAboard_schLib") (part "Res_0402"))
    )
    (comp (ref "R102")
      (value "0R")
      (footprint "RES0402")
      (fields
        (field (name "ASSEMBLY INFO") "NF")
        (field (name "MANUFACTURER") "Yageo")
        (field (name "TOLERANCE") "Jumper")
      )
      (libsource (lib "") (part "Res_0402_1"))
    )
    (comp (ref "SB1")
      (value "Solder bridge")
      (footprint "SOLDER_BRIDGE_TRIANGULAR_v2")
      (description "Can be shorted out using solder paste or 0402-1206 resistor")
      (fields (field (name "MANUFACTURER") "Yageo") (field (name "TOLERANCE") "Jumper"))
      (libsource (lib "LimeMicroAltiumLib_schLib_r03") (part "SOLDER_BRIDGE_TRIANGULAR"))
    )
    (comp (ref "SB2")
      (value "Solder bridge")
      (footprint "SOLDER_BRIDGE_TRIANGULAR_v2")
      (description "Can be shorted out using solder paste or 0402-1206 resistor")
      (fields (field (name "MANUFACTURER") "Yageo") (field (name "TOLERANCE") "Jumper"))
      (libsource (lib "LimeMicroAltiumLib_schLib_r03") (part "SOLDER_BRIDGE_TRIANGULAR"))
    )
    (comp (ref "SB3")
      (value "Solder bridge")
      (footprint "SOLDER_BRIDGE_TRIANGULAR_v2")
      (description "Can be shorted out using solder paste or 0402-1206 resistor")
      (fields (field (name "MANUFACTURER") "Yageo") (field (name "TOLERANCE") "Jumper"))
      (libsource (lib "LimeMicroAltiumLib_schLib_r03") (part "SOLDER_BRIDGE_TRIANGULAR"))
    )
    (comp (ref "SB4")
      (value "Solder bridge")
      (footprint "SOLDER_BRIDGE_TRIANGULAR_v2")
      (description "Can be shorted out using solder paste or 0402-1206 resistor")
      (fields (field (name "MANUFACTURER") "Yageo") (field (name "TOLERANCE") "Jumper"))
      (libsource (lib "LimeMicroAltiumLib_schLib_r03") (part "SOLDER_BRIDGE_TRIANGULAR"))
    )
    (comp (ref "VT4")
      (value "IRLML6244TRPBF")
      (footprint "SOT23-3")
      (description "NDS331N")
      (fields (field (name "MANUFACTURER") "Infineon Technologies"))
      (libsource (lib "LimeFPGAboard_schLib") (part "NDS331N"))
    )
    (comp (ref "XO1")
      (value "E7355LF, 40MHz, w VC")
      (footprint "RAKON_RTX5032A")
      (fields (field (name "MANUFACTURER") "Rakon"))
      (libsource (lib "LimeMicroAltiumLib_schLib") (part "Rakon_RTX5032A"))
    )
  )
  (nets
    (net (code "1") (name "+1.8V_DIG_LMK") (class "Default")
      (node (ref "C164") (pin "2") (pinfunction "2_2") (pintype "passive"))
      (node (ref "C171") (pin "2") (pinfunction "2_2") (pintype "passive"))
      (node (ref "C172") (pin "2") (pinfunction "2_2") (pintype "passive"))
      (node (ref "C173") (pin "2") (pinfunction "2_2") (pintype "passive"))
      (node (ref "FR40") (pin "2") (pinfunction "2_2") (pintype "passive"))
      (node (ref "IC9") (pin "2") (pinfunction "Vddo_2") (pintype "passive"))
      (node (ref "IC9") (pin "6") (pinfunction "Vddo_6") (pintype "passive"))
    )
    (net (code "2") (name "+3.3V_DIG_LMK") (class "Default")
      (node (ref "C165") (pin "2") (pinfunction "2_2") (pintype "passive"))
      (node (ref "C166") (pin "2") (pinfunction "2_2") (pintype "passive"))
      (node (ref "C167") (pin "2") (pinfunction "2_2") (pintype "passive"))
      (node (ref "C168") (pin "2") (pinfunction "2_2") (pintype "passive"))
      (node (ref "C169") (pin "2") (pinfunction "2_2") (pintype "passive"))
      (node (ref "C170") (pin "2") (pinfunction "2_2") (pintype "passive"))
      (node (ref "FR39") (pin "2") (pinfunction "2_2") (pintype "passive"))
      (node (ref "IC9") (pin "14") (pinfunction "Vddo_14") (pintype "passive"))
      (node (ref "IC9") (pin "18") (pinfunction "Vddo_18") (pintype "passive"))
      (node (ref "IC9") (pin "23") (pinfunction "Vdd_23") (pintype "passive"))
      (node (ref "IC9") (pin "8") (pinfunction "Vdd_8") (pintype "passive"))
      (node (ref "R61") (pin "2") (pinfunction "2_2") (pintype "passive"))
    )
    (net (code "3") (name "/CLK_SEL") (class "Default")
      (node (ref "IC20") (pin "6") (pinfunction "SEL_6") (pintype "passive"))
    )
    (net (code "4") (name "/EN_VCC3P3") (class "Default")
      (node (ref "C194") (pin "2") (pinfunction "2_2") (pintype "passive"))
      (node (ref "IC19") (pin "2") (pinfunction "EN_2") (pintype "input"))
      (node (ref "R86") (pin "1") (pinfunction "1_1") (pintype "passive"))
      (node (ref "R90") (pin "2") (pinfunction "2_2") (pintype "passive"))
      (node (ref "R93") (pin "1") (pinfunction "1_1") (pintype "passive"))
    )
    (net (code "5") (name "/FAN_CTRL") (class "Default")
      (node (ref "VT4") (pin "G") (pinfunction "G_G") (pintype "passive"))
    )
    (net (code "6") (name "/FPGA_CFG_SPI_MISO") (class "Default")
      (node (ref "IC15") (pin "2") (pinfunction "Q_2") (pintype "passive"))
    )
    (net (code "7") (name "/FPGA_CFG_SPI_MOSI") (class "Default")
      (node (ref "IC15") (pin "5") (pinfunction "D_5") (pintype "passive"))
    )
    (net (code "8") (name "/FPGA_CFG_SPI_SCLK") (class "Default")
      (node (ref "IC15") (pin "6") (pinfunction "C_6") (pintype "passive"))
      (node (ref "R75") (pin "1") (pinfunction "1_1") (pintype "passive"))
    )
    (net (code "9") (name "/FPGA_CFG_SPI_SS") (class "Default")
      (node (ref "IC15") (pin "1") (pinfunction "S_1") (pintype "passive"))
      (node (ref "R77") (pin "1") (pinfunction "1_1") (pintype "passive"))
    )
    (net (code "10") (name "/FPGA_GPIO4") (class "Default")
      (node (ref "SB1") (pin "2") (pinfunction "2_2") (pintype "passive"))
    )
    (net (code "11") (name "/FPGA_GPIO5") (class "Default")
      (node (ref "SB2") (pin "2") (pinfunction "2_2") (pintype "passive"))
    )
    (net (code "12") (name "/FPGA_GPIO6") (class "Default")
      (node (ref "SB3") (pin "2") (pinfunction "2_2") (pintype "passive"))
    )
    (net (code "13") (name "/FPGA_GPIO7") (class "Default")
      (node (ref "SB4") (pin "2") (pinfunction "2_2") (pintype "passive"))
    )
    (net (code "14") (name "/FPGA_I2C_SCL") (class "Default")
      (node (ref "IC10") (pin "2") (pinfunction "SCL_2") (pintype "passive"))
      (node (ref "IC12") (pin "6") (pinfunction "SCL_6") (pintype "input"))
      (node (ref "R70") (pin "2") (pinfunction "2_2") (pintype "passive"))
    )
    (net (code "15") (name "/FPGA_I2C_SDA") (class "Default")
      (node (ref "IC10") (pin "1") (pinfunction "SDA_1") (pintype "passive"))
      (node (ref "IC12") (pin "5") (pinfunction "SDA_5") (pintype "bidirectional"))
      (node (ref "R68") (pin "2") (pinfunction "2_2") (pintype "passive"))
    )
    (net (code "16") (name "/FPGA_LED1_G") (class "Default")
      (node (ref "R85") (pin "2") (pinfunction "2_2") (pintype "passive"))
    )
    (net (code "17") (name "/FPGA_LED1_R") (class "Default")
      (node (ref "R87") (pin "2") (pinfunction "2_2") (pintype "passive"))
    )
    (net (code "18") (name "/FPGA_LED2_G") (class "Default")
      (node (ref "R92") (pin "2") (pinfunction "2_2") (pintype "passive"))
      (node (ref "SB1") (pin "1") (pinfunction "1_1") (pintype "passive"))
    )
    (net (code "19") (name "/FPGA_LED2_R") (class "Default")
      (node (ref "R95") (pin "2") (pinfunction "2_2") (pintype "passive"))
      (node (ref "SB2") (pin "1") (pinfunction "1_1") (pintype "passive"))
    )
    (net (code "20") (name "/FPGA_LED3_G") (class "Default")
      (node (ref "R97") (pin "2") (pinfunction "2_2") (pintype "passive"))
      (node (ref "SB3") (pin "1") (pinfunction "1_1") (pintype "passive"))
    )
    (net (code "21") (name "/FPGA_LED3_R") (class "Default")
      (node (ref "R99") (pin "2") (pinfunction "2_2") (pintype "passive"))
      (node (ref "SB4") (pin "1") (pinfunction "1_1") (pintype "passive"))
    )
    (net (code "22") (name "/FPGA_SPI_DAC_SS") (class "Default")
      (node (ref "IC11") (pin "1") (pinfunction "~{SYNC}_1") (pintype "input"))
      (node (ref "IC16") (pin "5") (pinfunction "~{SYN}C_5") (pintype "input"))
    )
    (net (code "23") (name "/FPGA_SPI_MOSI") (class "Default")
      (node (ref "IC11") (pin "3") (pinfunction "SDIN_3") (pintype "input"))
      (node (ref "IC16") (pin "7") (pinfunction "DIN_7") (pintype "input"))
    )
    (net (code "24") (name "/FPGA_SPI_SCLK") (class "Default")
      (node (ref "IC11") (pin "2") (pinfunction "SCLK_2") (pintype "input"))
      (node (ref "IC16") (pin "6") (pinfunction "SCLK_6") (pintype "input"))
    )
    (net (code "25") (name "/LM75_OS") (class "Default")
      (node (ref "IC10") (pin "3") (pinfunction "OS_3") (pintype "passive"))
      (node (ref "R62") (pin "1") (pinfunction "1_1") (pintype "passive"))
    )
    (net (code "26") (name "/LMK_CLK") (class "Default")
      (node (ref "IC9") (pin "13") (pinfunction "CLKout2_13") (pintype "passive"))
    )
    (net (code "27") (name "/PG_VCC1P1") (class "Default")
      (node (ref "IC13") (pin "3") (pinfunction "PG_3") (pintype "output"))
      (node (ref "R90") (pin "1") (pinfunction "1_1") (pintype "passive"))
    )
    (net (code "28") (name "/REF_CLK_IN") (class "Default")
      (node (ref "IC20") (pin "1") (pinfunction "B1_1") (pintype "passive"))
      (node (ref "J8") (pin "1") (pinfunction "X_1") (pintype "passive"))
    )
    (net (code "29") (name "/REF_CLK_OUT") (class "Default")
      (node (ref "IC9") (pin "17") (pinfunction "CLKout4_17") (pintype "passive"))
      (node (ref "J7") (pin "1") (pinfunction "X_1") (pintype "passive"))
    )
    (net (code "30") (name "/RxPLL_CLK") (class "Default")
      (node (ref "C160") (pin "2") (pinfunction "2_2") (pintype "passive"))
      (node (ref "R69") (pin "1") (pinfunction "1_1") (pintype "passive"))
    )
    (net (code "31") (name "/TCXO_DAC_VREF") (class "Default")
      (node (ref "C183") (pin "1") (pinfunction "1_1") (pintype "passive"))
      (node (ref "IC16") (pin "2") (pinfunction "Vref_2") (pintype "input"))
      (node (ref "R76") (pin "1") (pinfunction "1_1") (pintype "passive"))
      (node (ref "R78") (pin "2") (pinfunction "2_2") (pintype "passive"))
      (node (ref "R81") (pin "1") (pinfunction "1_1") (pintype "passive"))
      (node (ref "R83") (pin "1") (pinfunction "1_1") (pintype "passive"))
    )
    (net (code "32") (name "/TxPLL_CLK") (class "Default")
      (node (ref "C158") (pin "2") (pinfunction "2_2") (pintype "passive"))
      (node (ref "R65") (pin "1") (pinfunction "1_1") (pintype "passive"))
    )
    (net (code "33") (name "/XO_VC") (class "Default")
      (node (ref "C163") (pin "2") (pinfunction "2_2") (pintype "passive"))
      (node (ref "C184") (pin "1") (pinfunction "1_1") (pintype "passive"))
      (node (ref "IC16") (pin "3") (pinfunction "Vfb_3") (pintype "input"))
      (node (ref "IC16") (pin "4") (pinfunction "Vout_4") (pintype "output"))
      (node (ref "R71") (pin "1") (pinfunction "1_1") (pintype "passive"))
      (node (ref "R72") (pin "1") (pinfunction "1_1") (pintype "passive"))
      (node (ref "R73") (pin "1") (pinfunction "1_1") (pintype "passive"))
      (node (ref "XO1") (pin "1") (pinfunction "VCO_1") (pintype "input"))
    )
    (net (code "34") (name "GND") (class "Default")
      (node (ref "C156") (pin "2") (pinfunction "2_2") (pintype "passive"))
      (node (ref "C157") (pin "1") (pinfunction "1_1") (pintype "passive"))
      (node (ref "C158") (pin "1") (pinfunction "1_1") (pintype "passive"))
      (node (ref "C159") (pin "1") (pinfunction "1_1") (pintype "passive"))
      (node (ref "C160") (pin "1") (pinfunction "1_1") (pintype "passive"))
      (node (ref "C161") (pin "1") (pinfunction "1_1") (pintype "passive"))
      (node (ref "C162") (pin "1") (pinfunction "1_1") (pintype "passive"))
      (node (ref "C163") (pin "1") (pinfunction "1_1") (pintype "passive"))
      (node (ref "C164") (pin "1") (pinfunction "1_1") (pintype "passive"))
      (node (ref "C165") (pin "1") (pinfunction "1_1") (pintype "passive"))
      (node (ref "C166") (pin "1") (pinfunction "1_1") (pintype "passive"))
      (node (ref "C167") (pin "1") (pinfunction "1_1") (pintype "passive"))
      (node (ref "C168") (pin "1") (pinfunction "1_1") (pintype "passive"))
      (node (ref "C169") (pin "1") (pinfunction "1_1") (pintype "passive"))
      (node (ref "C170") (pin "1") (pinfunction "1_1") (pintype "passive"))
      (node (ref "C171") (pin "1") (pinfunction "1_1") (pintype "passive"))
      (node (ref "C172") (pin "1") (pinfunction "1_1") (pintype "passive"))
      (node (ref "C173") (pin "1") (pinfunction "1_1") (pintype "passive"))
      (node (ref "C174") (pin "2") (pinfunction "2_2") (pintype "passive"))
      (node (ref "C175") (pin "2") (pinfunction "2_2") (pintype "passive"))
      (node (ref "C176") (pin "1") (pinfunction "1_1") (pintype "passive"))
      (node (ref "C177") (pin "1") (pinfunction "1_1") (pintype "passive"))
      (node (ref "C178") (pin "1") (pinfunction "1_1") (pintype "passive"))
      (node (ref "C179") (pin "1") (pinfunction "1_1") (pintype "passive"))
      (node (ref "C180") (pin "2") (pinfunction "2_2") (pintype "passive"))
      (node (ref "C181") (pin "2") (pinfunction "2_2") (pintype "passive"))
      (node (ref "C183") (pin "2") (pinfunction "2_2") (pintype "passive"))
      (node (ref "C184") (pin "2") (pinfunction "2_2") (pintype "passive"))
      (node (ref "C185") (pin "1") (pinfunction "1_1") (pintype "passive"))
      (node (ref "C186") (pin "1") (pinfunction "1_1") (pintype "passive"))
      (node (ref "C188") (pin "1") (pinfunction "1_1") (pintype "passive"))
      (node (ref "C189") (pin "1") (pinfunction "1_1") (pintype "passive"))
      (node (ref "C190") (pin "1") (pinfunction "1_1") (pintype "passive"))
      (node (ref "C191") (pin "1") (pinfunction "1_1") (pintype "passive"))
      (node (ref "C192") (pin "1") (pinfunction "1_1") (pintype "passive"))
      (node (ref "C194") (pin "1") (pinfunction "1_1") (pintype "passive"))
      (node (ref "C195") (pin "2") (pinfunction "2_2") (pintype "passive"))
      (node (ref "C196") (pin "1") (pinfunction "1_1") (pintype "passive"))
      (node (ref "C197") (pin "1") (pinfunction "1_1") (pintype "passive"))
      (node (ref "C198") (pin "1") (pinfunction "1_1") (pintype "passive"))
      (node (ref "IC10") (pin "4") (pinfunction "GND_4") (pintype "passive"))
      (node (ref "IC10") (pin "5") (pinfunction "A2_5") (pintype "passive"))
      (node (ref "IC10") (pin "6") (pinfunction "A1_6") (pintype "passive"))
      (node (ref "IC10") (pin "7") (pinfunction "A0_7") (pintype "passive"))
      (node (ref "IC11") (pin "5") (pinfunction "GND_5") (pintype "power_in"))
      (node (ref "IC12") (pin "1") (pinfunction "E0_1") (pintype "input"))
      (node (ref "IC12") (pin "2") (pinfunction "E1_2") (pintype "input"))
      (node (ref "IC12") (pin "3") (pinfunction "E2_3") (pintype "input"))
      (node (ref "IC12") (pin "4") (pinfunction "VSS_4") (pintype "power_in"))
      (node (ref "IC12") (pin "7") (pinfunction "~{WC}_7") (pintype "input"))
      (node (ref "IC12") (pin "PAD") (pinfunction "PAD_PAD") (pintype "power_in"))
      (node (ref "IC13") (pin "2") (pinfunction "GND_2") (pintype "passive"))
      (node (ref "IC13") (pin "PAD") (pinfunction "PAD_PAD") (pintype "passive"))
      (node (ref "IC14") (pin "3") (pinfunction "MODE_3") (pintype "input"))
      (node (ref "IC14") (pin "6") (pinfunction "GND_6") (pintype "power_in"))
      (node (ref "IC14") (pin "PAD") (pinfunction "EP_(GND)_PAD") (pintype "passive"))
      (node (ref "IC15") (pin "3") (pinfunction "W_3") (pintype "passive"))
      (node (ref "IC15") (pin "4") (pinfunction "GND_4") (pintype "passive"))
      (node (ref "IC15") (pin "PAD") (pinfunction "GND_PAD") (pintype "passive"))
      (node (ref "IC16") (pin "8") (pinfunction "GND_8") (pintype "passive"))
      (node (ref "IC17") (pin "3") (pinfunction "NC/A_3") (pintype "passive"))
      (node (ref "IC18") (pin "2") (pinfunction "GND_2") (pintype "passive"))
      (node (ref "IC18") (pin "PAD") (pinfunction "PAD_PAD") (pintype "passive"))
      (node (ref "IC19") (pin "3") (pinfunction "MODE_3") (pintype "input"))
      (node (ref "IC19") (pin "6") (pinfunction "GND_6") (pintype "power_in"))
      (node (ref "IC19") (pin "PAD") (pinfunction "EP_(GND)_PAD") (pintype "passive"))
      (node (ref "IC20") (pin "2") (pinfunction "GND_2") (pintype "passive"))
      (node (ref "IC9") (pin "1") (pinfunction "GND_1") (pintype "passive"))
      (node (ref "IC9") (pin "11") (pinfunction "GND_11") (pintype "passive"))
      (node (ref "IC9") (pin "12") (pinfunction "GND_12") (pintype "passive"))
      (node (ref "IC9") (pin "16") (pinfunction "GND_16") (pintype "passive"))
      (node (ref "IC9") (pin "19") (pinfunction "GND_19") (pintype "passive"))
      (node (ref "IC9") (pin "22") (pinfunction "SEL_22") (pintype "passive"))
      (node (ref "IC9") (pin "25") (pinfunction "GND_25") (pintype "passive"))
      (node (ref "IC9") (pin "7") (pinfunction "GND_7") (pintype "passive"))
      (node (ref "J7") (pin "2") (pinfunction "Y_2") (pintype "passive"))
      (node (ref "J8") (pin "2") (pinfunction "Y_2") (pintype "passive"))
      (node (ref "R100") (pin "1") (pinfunction "1_1") (pintype "passive"))
      (node (ref "R102") (pin "2") (pinfunction "2_2") (pintype "passive"))
      (node (ref "R67") (pin "1") (pinfunction "1_1") (pintype "passive"))
      (node (ref "R73") (pin "2") (pinfunction "2_2") (pintype "passive"))
      (node (ref "R80") (pin "2") (pinfunction "2_2") (pintype "passive"))
      (node (ref "R82") (pin "1") (pinfunction "1_1") (pintype "passive"))
      (node (ref "R83") (pin "2") (pinfunction "2_2") (pintype "passive"))
      (node (ref "R89") (pin "2") (pinfunction "2_2") (pintype "passive"))
      (node (ref "R91") (pin "1") (pinfunction "1_1") (pintype "passive"))
      (node (ref "VT4") (pin "S") (pinfunction "S_S") (pintype "passive"))
      (node (ref "XO1") (pin "4") (pinfunction "GND_4") (pintype "passive"))
    )
    (net (code "35") (name "Net-(C154-Pad1)") (class "Default")
      (node (ref "C154") (pin "1") (pinfunction "1_1") (pintype "passive"))
      (node (ref "C155") (pin "2") (pinfunction "2_2") (pintype "passive"))
      (node (ref "R67") (pin "2") (pinfunction "2_2") (pintype "passive"))
    )
    (net (code "36") (name "Net-(C159-Pad2)") (class "Default")
      (node (ref "C159") (pin "2") (pinfunction "2_2") (pintype "passive"))
      (node (ref "FR38") (pin "1") (pinfunction "1_1") (pintype "passive"))
      (node (ref "R64") (pin "1") (pinfunction "1_1") (pintype "passive"))
    )
    (net (code "37") (name "Net-(C195-Pad1)") (class "Default")
      (node (ref "C195") (pin "1") (pinfunction "1_1") (pintype "passive"))
      (node (ref "J9") (pin "2") (pinfunction "2_2") (pintype "passive"))
      (node (ref "R94") (pin "2") (pinfunction "2_2") (pintype "passive"))
      (node (ref "R96") (pin "2") (pinfunction "2_2") (pintype "passive"))
    )
    (net (code "38") (name "Net-(IC9-CLKin)") (class "Default")
      (node (ref "C155") (pin "1") (pinfunction "1_1") (pintype "passive"))
      (node (ref "IC9") (pin "21") (pinfunction "CLKin_21") (pintype "passive"))
    )
    (net (code "39") (name "Net-(IC9-CLKin*)") (class "Default")
      (node (ref "C162") (pin "2") (pinfunction "2_2") (pintype "passive"))
      (node (ref "IC9") (pin "20") (pinfunction "CLKin*_20") (pintype "passive"))
    )
    (net (code "40") (name "Net-(IC9-CLKout0)") (class "Default")
      (node (ref "IC9") (pin "3") (pinfunction "CLKout0_3") (pintype "passive"))
      (node (ref "R65") (pin "2") (pinfunction "2_2") (pintype "passive"))
    )
    (net (code "41") (name "Net-(IC9-CLKout1)") (class "Default")
      (node (ref "IC9") (pin "5") (pinfunction "CLKout1_5") (pintype "passive"))
      (node (ref "R69") (pin "2") (pinfunction "2_2") (pintype "passive"))
    )
    (net (code "42") (name "Net-(IC9-OE)") (class "Default")
      (node (ref "IC9") (pin "24") (pinfunction "OE_24") (pintype "passive"))
      (node (ref "R61") (pin "1") (pinfunction "1_1") (pintype "passive"))
    )
    (net (code "43") (name "Net-(IC11-VDD)") (class "Default")
      (node (ref "C175") (pin "1") (pinfunction "1_1") (pintype "passive"))
      (node (ref "FR41") (pin "2") (pinfunction "2_2") (pintype "passive"))
      (node (ref "IC11") (pin "4") (pinfunction "VDD_4") (pintype "power_in"))
    )
    (net (code "44") (name "Net-(IC11-VOUT)") (class "Default")
      (node (ref "IC11") (pin "6") (pinfunction "VOUT_6") (pintype "tri_state"))
      (node (ref "R72") (pin "2") (pinfunction "2_2") (pintype "passive"))
    )
    (net (code "45") (name "Net-(IC13-ADJ)") (class "Default")
      (node (ref "IC13") (pin "5") (pinfunction "ADJ_5") (pintype "input"))
      (node (ref "R74") (pin "1") (pinfunction "1_1") (pintype "passive"))
      (node (ref "R80") (pin "1") (pinfunction "1_1") (pintype "passive"))
    )
    (net (code "46") (name "Net-(IC14-FB)") (class "Default")
      (node (ref "C182") (pin "2") (pinfunction "2_2") (pintype "passive"))
      (node (ref "IC14") (pin "4") (pinfunction "FB_4") (pintype "input"))
      (node (ref "R79") (pin "1") (pinfunction "1_1") (pintype "passive"))
      (node (ref "R82") (pin "2") (pinfunction "2_2") (pintype "passive"))
    )
    (net (code "47") (name "Net-(IC16-Vdd)") (class "Default")
      (node (ref "C180") (pin "1") (pinfunction "1_1") (pintype "passive"))
      (node (ref "FR42") (pin "2") (pinfunction "2_2") (pintype "passive"))
      (node (ref "IC16") (pin "1") (pinfunction "Vdd_1") (pintype "power_in"))
      (node (ref "R76") (pin "2") (pinfunction "2_2") (pintype "passive"))
    )
    (net (code "48") (name "Net-(IC17-A)") (class "Default")
      (node (ref "IC17") (pin "2") (pinfunction "A_2") (pintype "passive"))
      (node (ref "R102") (pin "1") (pinfunction "1_1") (pintype "passive"))
      (node (ref "R66") (pin "2") (pinfunction "2_2") (pintype "passive"))
    )
    (net (code "49") (name "Net-(IC18-ADJ)") (class "Default")
      (node (ref "IC18") (pin "5") (pinfunction "ADJ_5") (pintype "input"))
      (node (ref "R84") (pin "1") (pinfunction "1_1") (pintype "passive"))
      (node (ref "R89") (pin "1") (pinfunction "1_1") (pintype "passive"))
    )
    (net (code "50") (name "Net-(IC18-PG)") (class "Default")
      (node (ref "C192") (pin "2") (pinfunction "2_2") (pintype "passive"))
      (node (ref "IC18") (pin "3") (pinfunction "PG_3") (pintype "output"))
    )
    (net (code "51") (name "Net-(IC19-FB)") (class "Default")
      (node (ref "C193") (pin "2") (pinfunction "2_2") (pintype "passive"))
      (node (ref "IC19") (pin "4") (pinfunction "FB_4") (pintype "input"))
      (node (ref "R88") (pin "1") (pinfunction "1_1") (pintype "passive"))
      (node (ref "R91") (pin "2") (pinfunction "2_2") (pintype "passive"))
    )
    (net (code "52") (name "Net-(IC20-A)") (class "Default")
      (node (ref "C154") (pin "2") (pinfunction "2_2") (pintype "passive"))
      (node (ref "IC20") (pin "4") (pinfunction "A_4") (pintype "passive"))
    )
    (net (code "53") (name "Net-(IC20-B0)") (class "Default")
      (node (ref "IC20") (pin "3") (pinfunction "B0_3") (pintype "passive"))
      (node (ref "XO1") (pin "6") (pinfunction "RF_OUT_6") (pintype "output"))
    )
    (net (code "54") (name "Net-(J9-Pad1)") (class "Default")
      (node (ref "J9") (pin "1") (pinfunction "1_1") (pintype "passive"))
      (node (ref "R100") (pin "2") (pinfunction "2_2") (pintype "passive"))
      (node (ref "VT4") (pin "D") (pinfunction "D_D") (pintype "passive"))
    )
    (net (code "55") (name "Net-(LED1-Pad3)") (class "Default")
      (node (ref "LED1") (pin "3") (pinfunction "3_3") (pintype "power_in"))
      (node (ref "R85") (pin "1") (pinfunction "1_1") (pintype "passive"))
    )
    (net (code "56") (name "Net-(LED1-Pad4)") (class "Default")
      (node (ref "LED1") (pin "4") (pinfunction "4_4") (pintype "power_in"))
      (node (ref "R87") (pin "1") (pinfunction "1_1") (pintype "passive"))
    )
    (net (code "57") (name "Net-(LED2-Pad3)") (class "Default")
      (node (ref "LED2") (pin "3") (pinfunction "3_3") (pintype "power_in"))
      (node (ref "R92") (pin "1") (pinfunction "1_1") (pintype "passive"))
    )
    (net (code "58") (name "Net-(LED2-Pad4)") (class "Default")
      (node (ref "LED2") (pin "4") (pinfunction "4_4") (pintype "power_in"))
      (node (ref "R95") (pin "1") (pinfunction "1_1") (pintype "passive"))
    )
    (net (code "59") (name "Net-(LED3-Pad3)") (class "Default")
      (node (ref "LED3") (pin "3") (pinfunction "3_3") (pintype "power_in"))
      (node (ref "R97") (pin "1") (pinfunction "1_1") (pintype "passive"))
    )
    (net (code "60") (name "Net-(LED3-Pad4)") (class "Default")
      (node (ref "LED3") (pin "4") (pinfunction "4_4") (pintype "power_in"))
      (node (ref "R99") (pin "1") (pinfunction "1_1") (pintype "passive"))
    )
    (net (code "61") (name "Net-(XO1-VC_FILTER)") (class "Default")
      (node (ref "C157") (pin "2") (pinfunction "2_2") (pintype "passive"))
      (node (ref "XO1") (pin "7") (pinfunction "VC_FILTER_7") (pintype "input"))
    )
    (net (code "62") (name "VCC1P1") (class "Default")
      (node (ref "C179") (pin "2") (pinfunction "2_2") (pintype "passive"))
      (node (ref "IC13") (pin "4") (pinfunction "Vout_4") (pintype "output"))
      (node (ref "R74") (pin "2") (pinfunction "2_2") (pintype "passive"))
    )
    (net (code "63") (name "VCC1P8") (class "Default")
      (node (ref "C177") (pin "2") (pinfunction "2_2") (pintype "passive"))
      (node (ref "C178") (pin "2") (pinfunction "2_2") (pintype "passive"))
      (node (ref "C182") (pin "1") (pinfunction "1_1") (pintype "passive"))
      (node (ref "FR40") (pin "1") (pinfunction "1_1") (pintype "passive"))
      (node (ref "IC13") (pin "1") (pinfunction "EN_1") (pintype "input"))
      (node (ref "IC13") (pin "6") (pinfunction "Vin_6") (pintype "input"))
      (node (ref "IC14") (pin "5") (pinfunction "VOUT_5") (pintype "output"))
      (node (ref "R62") (pin "2") (pinfunction "2_2") (pintype "passive"))
      (node (ref "R79") (pin "2") (pinfunction "2_2") (pintype "passive"))
      (node (ref "R93") (pin "2") (pinfunction "2_2") (pintype "passive"))
    )
    (net (code "64") (name "VCC2P5") (class "Default")
      (node (ref "C191") (pin "2") (pinfunction "2_2") (pintype "passive"))
      (node (ref "IC18") (pin "4") (pinfunction "Vout_4") (pintype "output"))
      (node (ref "R81") (pin "2") (pinfunction "2_2") (pintype "passive"))
      (node (ref "R84") (pin "2") (pinfunction "2_2") (pintype "passive"))
      (node (ref "R98") (pin "1") (pinfunction "1_1") (pintype "passive"))
    )
    (net (code "65") (name "VCC2P5_VREF") (class "Default")
      (node (ref "C186") (pin "2") (pinfunction "2_2") (pintype "passive"))
      (node (ref "IC17") (pin "1") (pinfunction "K_1") (pintype "passive"))
      (node (ref "R63") (pin "1") (pinfunction "1_1") (pintype "passive"))
      (node (ref "R66") (pin "1") (pinfunction "1_1") (pintype "passive"))
      (node (ref "R78") (pin "1") (pinfunction "1_1") (pintype "passive"))
    )
    (net (code "66") (name "VCC3P3") (class "Default")
      (node (ref "C156") (pin "1") (pinfunction "1_1") (pintype "passive"))
      (node (ref "C174") (pin "1") (pinfunction "1_1") (pintype "passive"))
      (node (ref "C181") (pin "1") (pinfunction "1_1") (pintype "passive"))
      (node (ref "C189") (pin "2") (pinfunction "2_2") (pintype "passive"))
      (node (ref "C190") (pin "2") (pinfunction "2_2") (pintype "passive"))
      (node (ref "C193") (pin "1") (pinfunction "1_1") (pintype "passive"))
      (node (ref "FR44") (pin "1") (pinfunction "1_1") (pintype "passive"))
      (node (ref "IC10") (pin "8") (pinfunction "VCC_8") (pintype "passive"))
      (node (ref "IC12") (pin "8") (pinfunction "VCC_8") (pintype "power_in"))
      (node (ref "IC15") (pin "7") (pinfunction "HOLD_7") (pintype "passive"))
      (node (ref "IC15") (pin "8") (pinfunction "VCC_8") (pintype "passive"))
      (node (ref "IC18") (pin "1") (pinfunction "EN_1") (pintype "input"))
      (node (ref "IC18") (pin "6") (pinfunction "Vin_6") (pintype "input"))
      (node (ref "IC19") (pin "5") (pinfunction "VOUT_5") (pintype "output"))
      (node (ref "LED1") (pin "1") (pinfunction "1_1") (pintype "power_in"))
      (node (ref "LED1") (pin "2") (pinfunction "2_2") (pintype "power_in"))
      (node (ref "LED2") (pin "1") (pinfunction "1_1") (pintype "power_in"))
      (node (ref "LED2") (pin "2") (pinfunction "2_2") (pintype "power_in"))
      (node (ref "LED3") (pin "1") (pinfunction "1_1") (pintype "power_in"))
      (node (ref "LED3") (pin "2") (pinfunction "2_2") (pintype "power_in"))
      (node (ref "R101") (pin "1") (pinfunction "1_1") (pintype "passive"))
      (node (ref "R68") (pin "1") (pinfunction "1_1") (pintype "passive"))
      (node (ref "R70") (pin "1") (pinfunction "1_1") (pintype "passive"))
      (node (ref "R75") (pin "2") (pinfunction "2_2") (pintype "passive"))
      (node (ref "R77") (pin "2") (pinfunction "2_2") (pintype "passive"))
      (node (ref "R88") (pin "2") (pinfunction "2_2") (pintype "passive"))
      (node (ref "R96") (pin "1") (pinfunction "1_1") (pintype "passive"))
    )
    (net (code "67") (name "VCC3P3_CLK") (class "Default")
      (node (ref "C185") (pin "2") (pinfunction "2_2") (pintype "passive"))
      (node (ref "C196") (pin "2") (pinfunction "2_2") (pintype "passive"))
      (node (ref "FR39") (pin "1") (pinfunction "1_1") (pintype "passive"))
      (node (ref "FR41") (pin "1") (pinfunction "1_1") (pintype "passive"))
      (node (ref "FR42") (pin "1") (pinfunction "1_1") (pintype "passive"))
      (node (ref "FR44") (pin "2") (pinfunction "2_2") (pintype "passive"))
      (node (ref "IC20") (pin "5") (pinfunction "VCC_5") (pintype "passive"))
      (node (ref "R63") (pin "2") (pinfunction "2_2") (pintype "passive"))
      (node (ref "R64") (pin "2") (pinfunction "2_2") (pintype "passive"))
    )
    (net (code "68") (name "VCC3P3_XO") (class "Default")
      (node (ref "C161") (pin "2") (pinfunction "2_2") (pintype "passive"))
      (node (ref "FR38") (pin "2") (pinfunction "2_2") (pintype "passive"))
      (node (ref "R71") (pin "2") (pinfunction "2_2") (pintype "passive"))
      (node (ref "XO1") (pin "9") (pinfunction "VCC_9") (pintype "power_in"))
    )
    (net (code "69") (name "VCC5P0") (class "Default")
      (node (ref "C176") (pin "2") (pinfunction "2_2") (pintype "passive"))
      (node (ref "C188") (pin "2") (pinfunction "2_2") (pintype "passive"))
      (node (ref "IC14") (pin "2") (pinfunction "EN_2") (pintype "input"))
      (node (ref "IC14") (pin "8") (pinfunction "VIN_8") (pintype "power_in"))
      (node (ref "IC19") (pin "8") (pinfunction "VIN_8") (pintype "power_in"))
      (node (ref "R86") (pin "2") (pinfunction "2_2") (pintype "passive"))
      (node (ref "R94") (pin "1") (pinfunction "1_1") (pintype "passive"))
    )
    (net (code "70") (name "VDIO_LMS") (class "Default")
      (node (ref "C198") (pin "2") (pinfunction "2_2") (pintype "passive"))
      (node (ref "FR45") (pin "2") (pinfunction "2_2") (pintype "passive"))
    )
    (net (code "71") (name "VDIO_LMS_FPGA") (class "Default")
      (node (ref "C197") (pin "2") (pinfunction "2_2") (pintype "passive"))
      (node (ref "FR45") (pin "1") (pinfunction "1_1") (pintype "passive"))
      (node (ref "R101") (pin "2") (pinfunction "2_2") (pintype "passive"))
      (node (ref "R98") (pin "2") (pinfunction "2_2") (pintype "passive"))
    )
    (net (code "72") (name "unconnected-(IC9-CLKout3-Pad15)") (class "Default")
      (node (ref "IC9") (pin "15") (pinfunction "CLKout3_15") (pintype "passive+no_connect"))
    )
    (net (code "73") (name "unconnected-(IC9-OSCin-Pad9)") (class "Default")
      (node (ref "IC9") (pin "9") (pinfunction "OSCin_9") (pintype "passive+no_connect"))
    )
    (net (code "74") (name "unconnected-(IC9-OSCout-Pad10)") (class "Default")
      (node (ref "IC9") (pin "10") (pinfunction "OSCout_10") (pintype "passive+no_connect"))
    )
    (net (code "75") (name "unconnected-(IC14-NC-Pad7)") (class "Default")
      (node (ref "IC14") (pin "7") (pinfunction "NC_7") (pintype "passive+no_connect"))
    )
    (net (code "76") (name "unconnected-(IC14-PG-Pad1)") (class "Default")
      (node (ref "IC14") (pin "1") (pinfunction "PG_1") (pintype "output+no_connect"))
    )
    (net (code "77") (name "unconnected-(IC19-NC-Pad7)") (class "Default")
      (node (ref "IC19") (pin "7") (pinfunction "NC_7") (pintype "passive+no_connect"))
    )
    (net (code "78") (name "unconnected-(IC19-PG-Pad1)") (class "Default")
      (node (ref "IC19") (pin "1") (pinfunction "PG_1") (pintype "output+no_connect"))
    )
    (net (code "79") (name "unconnected-(XO1-NC-Pad2)") (class "Default")
      (node (ref "XO1") (pin "2") (pinfunction "NC_2") (pintype "passive+no_connect"))
    )
    (net (code "80") (name "unconnected-(XO1-NC-Pad3)") (class "Default")
      (node (ref "XO1") (pin "3") (pinfunction "NC_3") (pintype "passive+no_connect"))
    )
    (net (code "81") (name "unconnected-(XO1-NC-Pad5)") (class "Default")
      (node (ref "XO1") (pin "5") (pinfunction "NC_5") (pintype "passive+no_connect"))
    )
    (net (code "82") (name "unconnected-(XO1-NC-Pad8)") (class "Default")
      (node (ref "XO1") (pin "8") (pinfunction "NC_8") (pintype "passive+no_connect"))
    )
    (net (code "83") (name "unconnected-(XO1-NC-Pad10)") (class "Default")
      (node (ref "XO1") (pin "10") (pinfunction "NC_10") (pintype "passive+no_connect"))
    )
  )
)
